# mini-RGBWW.net
KiCad netlist of a schematic drawn in EAGLE
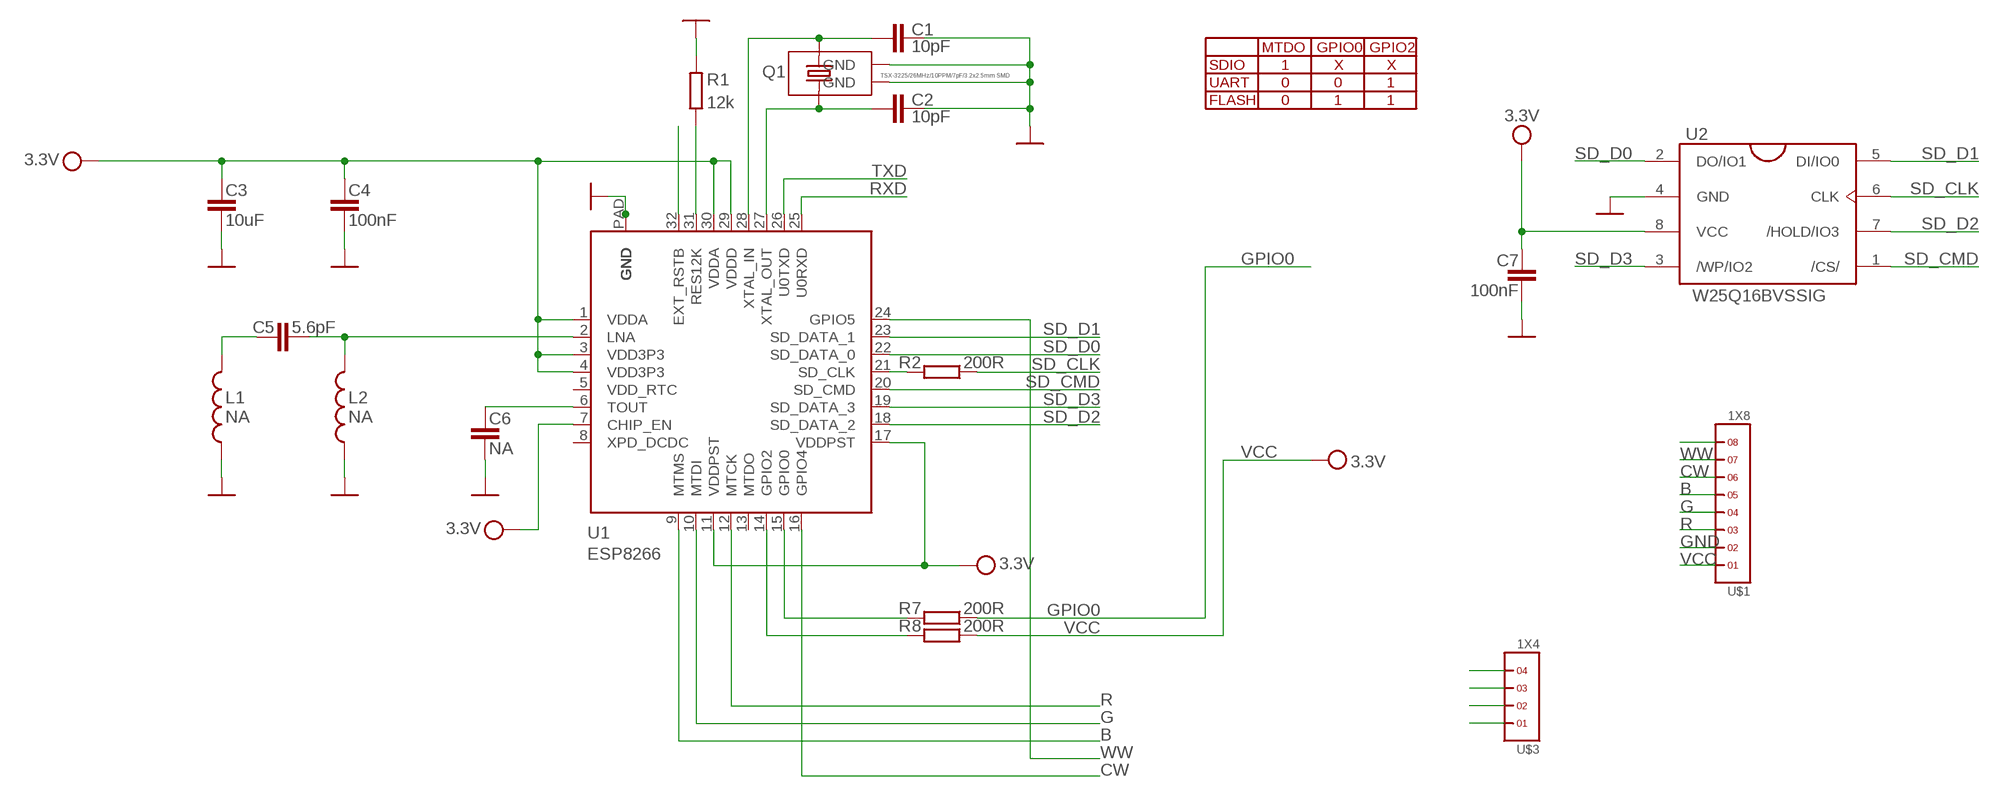
[diagram p0: schematic, sheet 1]

(export (version "E")
  (design (tool "Eeschema 10.0.6"))
  (components
    (comp (ref "C1")
      (value "10pF")
      (footprint "eagle-import:C0402_TI")
      (libsource (lib "eagle-import") (part "C-EUC0402_TI"))
    )
    (comp (ref "C2")
      (value "10pF")
      (footprint "eagle-import:C0402_TI")
      (libsource (lib "eagle-import") (part "C-EUC0402_TI"))
    )
    (comp (ref "C3")
      (value "10uF")
      (footprint "eagle-import:C0603_DWS")
      (libsource (lib "eagle-import") (part "C-EUC0603_DWS"))
    )
    (comp (ref "C4")
      (value "100nF")
      (footprint "eagle-import:C0402_TI")
      (libsource (lib "eagle-import") (part "C-EUC0402_TI"))
    )
    (comp (ref "C5")
      (value "5.6pF")
      (footprint "eagle-import:C0402_TI")
      (libsource (lib "eagle-import") (part "C-EUC0402_TI"))
    )
    (comp (ref "C6")
      (value "NA")
      (footprint "eagle-import:C0402_TI")
      (libsource (lib "eagle-import") (part "C-EUC0402_TI"))
    )
    (comp (ref "C7")
      (value "100nF")
      (footprint "eagle-import:C0402_TI")
      (libsource (lib "eagle-import") (part "C-EUC0402_TI"))
    )
    (comp (ref "L1")
      (value "NA")
      (footprint "eagle-import:L0402_TI")
      (libsource (lib "eagle-import") (part "L-USL0402_TI"))
    )
    (comp (ref "L2")
      (value "NA")
      (footprint "eagle-import:L0402_TI")
      (libsource (lib "eagle-import") (part "L-USL0402_TI"))
    )
    (comp (ref "Q1")
      (value "TSX-3225/26MHz/10PPM/7pF/3.2x2.5mm SMD")
      (footprint "eagle-import:NX3225SA")
      (libsource (lib "eagle-import") (part "SMALL_SMD_CRYSTAL_1"))
    )
    (comp (ref "R1")
      (value "12k")
      (footprint "eagle-import:R0402_TI")
      (libsource (lib "eagle-import") (part "R-EU_R0402_TI"))
    )
    (comp (ref "R2")
      (value "200R")
      (footprint "eagle-import:R0402_TI")
      (libsource (lib "eagle-import") (part "R-EU_R0402_TI"))
    )
    (comp (ref "R7")
      (value "200R")
      (footprint "eagle-import:R0402_TI")
      (libsource (lib "eagle-import") (part "R-EU_R0402_TI"))
    )
    (comp (ref "R8")
      (value "200R")
      (footprint "eagle-import:R0402_TI")
      (libsource (lib "eagle-import") (part "R-EU_R0402_TI"))
    )
    (comp (ref "U$1")
      (value "1X8")
      (footprint "eagle-import:1X8")
      (libsource (lib "eagle-import") (part "1X8"))
    )
    (comp (ref "U$3")
      (value "1X4")
      (footprint "eagle-import:1X4")
      (libsource (lib "eagle-import") (part "1X4"))
    )
    (comp (ref "U1")
      (value "ESP8266")
      (footprint "eagle-import:QFN32_PAD")
      (libsource (lib "eagle-import") (part "ESP8266"))
    )
    (comp (ref "U2")
      (value "W25Q16BVSSIG")
      (footprint "eagle-import:SO8_ATMEL_FLASH")
      (libsource (lib "eagle-import") (part "W25Q16BVSSIG"))
    )
  )
  (nets
    (net (code "1") (name "/B") (class "Default")
      (node (ref "U$1") (pin "5") (pinfunction "5_5") (pintype "bidirectional"))
      (node (ref "U1") (pin "9") (pinfunction "MTMS_9") (pintype "bidirectional"))
    )
    (net (code "2") (name "/CW") (class "Default")
      (node (ref "U$1") (pin "6") (pinfunction "6_6") (pintype "bidirectional"))
      (node (ref "U1") (pin "16") (pinfunction "GPIO4_16") (pintype "bidirectional"))
    )
    (net (code "3") (name "/G") (class "Default")
      (node (ref "U$1") (pin "4") (pinfunction "4_4") (pintype "bidirectional"))
      (node (ref "U1") (pin "10") (pinfunction "MTDI_10") (pintype "bidirectional"))
    )
    (net (code "4") (name "/GPIO0") (class "Default")
      (node (ref "R7") (pin "1") (pinfunction "1_1") (pintype "passive"))
      (node (ref "U$3") (pin "1") (pinfunction "1_1") (pintype "bidirectional"))
    )
    (net (code "5") (name "/R") (class "Default")
      (node (ref "U$1") (pin "3") (pinfunction "3_3") (pintype "bidirectional"))
      (node (ref "U1") (pin "12") (pinfunction "MTCK_12") (pintype "bidirectional"))
    )
    (net (code "6") (name "/RST") (class "Default")
      (node (ref "U$3") (pin "2") (pinfunction "2_2") (pintype "bidirectional"))
      (node (ref "U1") (pin "32") (pinfunction "EXT_RSTB_32") (pintype "bidirectional"))
    )
    (net (code "7") (name "/RXD") (class "Default")
      (node (ref "U$3") (pin "3") (pinfunction "3_3") (pintype "bidirectional"))
      (node (ref "U1") (pin "25") (pinfunction "U0RXD_25") (pintype "bidirectional"))
    )
    (net (code "8") (name "/SD_CLK") (class "Default")
      (node (ref "R2") (pin "1") (pinfunction "1_1") (pintype "passive"))
      (node (ref "U2") (pin "6") (pinfunction "CLK_6") (pintype "input"))
    )
    (net (code "9") (name "/SD_CMD") (class "Default")
      (node (ref "U1") (pin "20") (pinfunction "SD_CMD_20") (pintype "bidirectional"))
      (node (ref "U2") (pin "1") (pinfunction "/CS/_1") (pintype "input"))
    )
    (net (code "10") (name "/SD_D0") (class "Default")
      (node (ref "U1") (pin "22") (pinfunction "SD_DATA_0_22") (pintype "bidirectional"))
      (node (ref "U2") (pin "2") (pinfunction "DO/IO1_2") (pintype "bidirectional"))
    )
    (net (code "11") (name "/SD_D1") (class "Default")
      (node (ref "U1") (pin "23") (pinfunction "SD_DATA_1_23") (pintype "bidirectional"))
      (node (ref "U2") (pin "5") (pinfunction "DI/IO0_5") (pintype "bidirectional"))
    )
    (net (code "12") (name "/SD_D2") (class "Default")
      (node (ref "U1") (pin "18") (pinfunction "SD_DATA_2_18") (pintype "bidirectional"))
      (node (ref "U2") (pin "7") (pinfunction "/HOLD/IO3_7") (pintype "input"))
    )
    (net (code "13") (name "/SD_D3") (class "Default")
      (node (ref "U1") (pin "19") (pinfunction "SD_DATA_3_19") (pintype "bidirectional"))
      (node (ref "U2") (pin "3") (pinfunction "/WP/IO2_3") (pintype "input"))
    )
    (net (code "14") (name "/TXD") (class "Default")
      (node (ref "U$3") (pin "4") (pinfunction "4_4") (pintype "bidirectional"))
      (node (ref "U1") (pin "26") (pinfunction "U0TXD_26") (pintype "bidirectional"))
    )
    (net (code "15") (name "/WW") (class "Default")
      (node (ref "U$1") (pin "7") (pinfunction "7_7") (pintype "bidirectional"))
      (node (ref "U1") (pin "24") (pinfunction "GPIO5_24") (pintype "bidirectional"))
    )
    (net (code "16") (name "3.3V") (class "Default")
      (node (ref "C3") (pin "1") (pinfunction "1_1") (pintype "passive"))
      (node (ref "C4") (pin "1") (pinfunction "1_1") (pintype "passive"))
      (node (ref "C7") (pin "1") (pinfunction "1_1") (pintype "passive"))
      (node (ref "R8") (pin "1") (pinfunction "1_1") (pintype "passive"))
      (node (ref "U$1") (pin "1") (pinfunction "1_1") (pintype "bidirectional"))
      (node (ref "U1") (pin "1") (pinfunction "VDDA_1") (pintype "bidirectional"))
      (node (ref "U1") (pin "11") (pinfunction "VDDPST_11") (pintype "bidirectional"))
      (node (ref "U1") (pin "17") (pinfunction "VDDPST_17") (pintype "bidirectional"))
      (node (ref "U1") (pin "29") (pinfunction "VDDD_29") (pintype "bidirectional"))
      (node (ref "U1") (pin "3") (pinfunction "VDD3P3_3") (pintype "bidirectional"))
      (node (ref "U1") (pin "30") (pinfunction "VDDA_30") (pintype "bidirectional"))
      (node (ref "U1") (pin "4") (pinfunction "VDD3P3_4") (pintype "bidirectional"))
      (node (ref "U1") (pin "7") (pinfunction "CHIP_EN_7") (pintype "bidirectional"))
      (node (ref "U2") (pin "8") (pinfunction "VCC_8") (pintype "power_in"))
    )
    (net (code "17") (name "GND") (class "Default")
      (node (ref "C1") (pin "1") (pinfunction "1_1") (pintype "passive"))
      (node (ref "C2") (pin "1") (pinfunction "1_1") (pintype "passive"))
      (node (ref "C3") (pin "2") (pinfunction "2_2") (pintype "passive"))
      (node (ref "C4") (pin "2") (pinfunction "2_2") (pintype "passive"))
      (node (ref "C6") (pin "2") (pinfunction "2_2") (pintype "passive"))
      (node (ref "C7") (pin "2") (pinfunction "2_2") (pintype "passive"))
      (node (ref "L1") (pin "1") (pinfunction "1_1") (pintype "passive"))
      (node (ref "L2") (pin "1") (pinfunction "1_1") (pintype "passive"))
      (node (ref "Q1") (pin "NC_1") (pinfunction "GND_NC_1") (pintype "power_in"))
      (node (ref "Q1") (pin "NC_2") (pinfunction "GND_NC_2") (pintype "power_in"))
      (node (ref "R1") (pin "2") (pinfunction "2_2") (pintype "passive"))
      (node (ref "U$1") (pin "2") (pinfunction "2_2") (pintype "bidirectional"))
      (node (ref "U1") (pin "P$1") (pinfunction "GND_P$1") (pintype "bidirectional"))
      (node (ref "U1") (pin "P$2") (pinfunction "GND_P$2") (pintype "bidirectional"))
      (node (ref "U1") (pin "P$3") (pinfunction "GND_P$3") (pintype "bidirectional"))
      (node (ref "U1") (pin "P$4") (pinfunction "GND_P$4") (pintype "bidirectional"))
      (node (ref "U1") (pin "P$5") (pinfunction "GND_P$5") (pintype "bidirectional"))
      (node (ref "U1") (pin "P$6") (pinfunction "GND_P$6") (pintype "bidirectional"))
      (node (ref "U1") (pin "P$7") (pinfunction "GND_P$7") (pintype "bidirectional"))
      (node (ref "U1") (pin "P$8") (pinfunction "GND_P$8") (pintype "bidirectional"))
      (node (ref "U1") (pin "P$9") (pinfunction "GND_P$9") (pintype "bidirectional"))
      (node (ref "U1") (pin "PAD") (pinfunction "GND_PAD") (pintype "bidirectional"))
      (node (ref "U2") (pin "4") (pinfunction "GND_4") (pintype "power_in"))
    )
    (net (code "18") (name "Net-(C5-Pad1)") (class "Default")
      (node (ref "C5") (pin "1") (pinfunction "1_1") (pintype "passive"))
      (node (ref "L1") (pin "2") (pinfunction "2_2") (pintype "passive"))
    )
    (net (code "19") (name "Net-(U1-GPIO0)") (class "Default")
      (node (ref "R7") (pin "2") (pinfunction "2_2") (pintype "passive"))
      (node (ref "U1") (pin "15") (pinfunction "GPIO0_15") (pintype "bidirectional"))
    )
    (net (code "20") (name "Net-(U1-GPIO2)") (class "Default")
      (node (ref "R8") (pin "2") (pinfunction "2_2") (pintype "passive"))
      (node (ref "U1") (pin "14") (pinfunction "GPIO2_14") (pintype "bidirectional"))
    )
    (net (code "21") (name "Net-(U1-LNA)") (class "Default")
      (node (ref "C5") (pin "2") (pinfunction "2_2") (pintype "passive"))
      (node (ref "L2") (pin "2") (pinfunction "2_2") (pintype "passive"))
      (node (ref "U1") (pin "2") (pinfunction "LNA_2") (pintype "bidirectional"))
    )
    (net (code "22") (name "Net-(U1-RES12K)") (class "Default")
      (node (ref "R1") (pin "1") (pinfunction "1_1") (pintype "passive"))
      (node (ref "U1") (pin "31") (pinfunction "RES12K_31") (pintype "bidirectional"))
    )
    (net (code "23") (name "Net-(U1-SD_CLK)") (class "Default")
      (node (ref "R2") (pin "2") (pinfunction "2_2") (pintype "passive"))
      (node (ref "U1") (pin "21") (pinfunction "SD_CLK_21") (pintype "bidirectional"))
    )
    (net (code "24") (name "Net-(U1-TOUT)") (class "Default")
      (node (ref "C6") (pin "1") (pinfunction "1_1") (pintype "passive"))
      (node (ref "U1") (pin "6") (pinfunction "TOUT_6") (pintype "bidirectional"))
    )
    (net (code "25") (name "Net-(U1-XTAL_IN)") (class "Default")
      (node (ref "C1") (pin "2") (pinfunction "2_2") (pintype "passive"))
      (node (ref "Q1") (pin "1") (pinfunction "1_1") (pintype "input"))
      (node (ref "U1") (pin "28") (pinfunction "XTAL_IN_28") (pintype "bidirectional"))
    )
    (net (code "26") (name "Net-(U1-XTAL_OUT)") (class "Default")
      (node (ref "C2") (pin "2") (pinfunction "2_2") (pintype "passive"))
      (node (ref "Q1") (pin "2") (pinfunction "2_2") (pintype "input"))
      (node (ref "U1") (pin "27") (pinfunction "XTAL_OUT_27") (pintype "bidirectional"))
    )
    (net (code "27") (name "unconnected-(U$1-Pad8)") (class "Default")
      (node (ref "U$1") (pin "8") (pinfunction "8_8") (pintype "bidirectional"))
    )
    (net (code "28") (name "unconnected-(U1-MTDO-Pad13)") (class "Default")
      (node (ref "U1") (pin "13") (pinfunction "MTDO_13") (pintype "bidirectional"))
    )
    (net (code "29") (name "unconnected-(U1-VDD_RTC-Pad5)") (class "Default")
      (node (ref "U1") (pin "5") (pinfunction "VDD_RTC_5") (pintype "bidirectional"))
    )
    (net (code "30") (name "unconnected-(U1-XPD_DCDC-Pad8)") (class "Default")
      (node (ref "U1") (pin "8") (pinfunction "XPD_DCDC_8") (pintype "bidirectional"))
    )
  )
)
